# LTC6820.net
KiCad netlist of a schematic drawn in Altium Designer
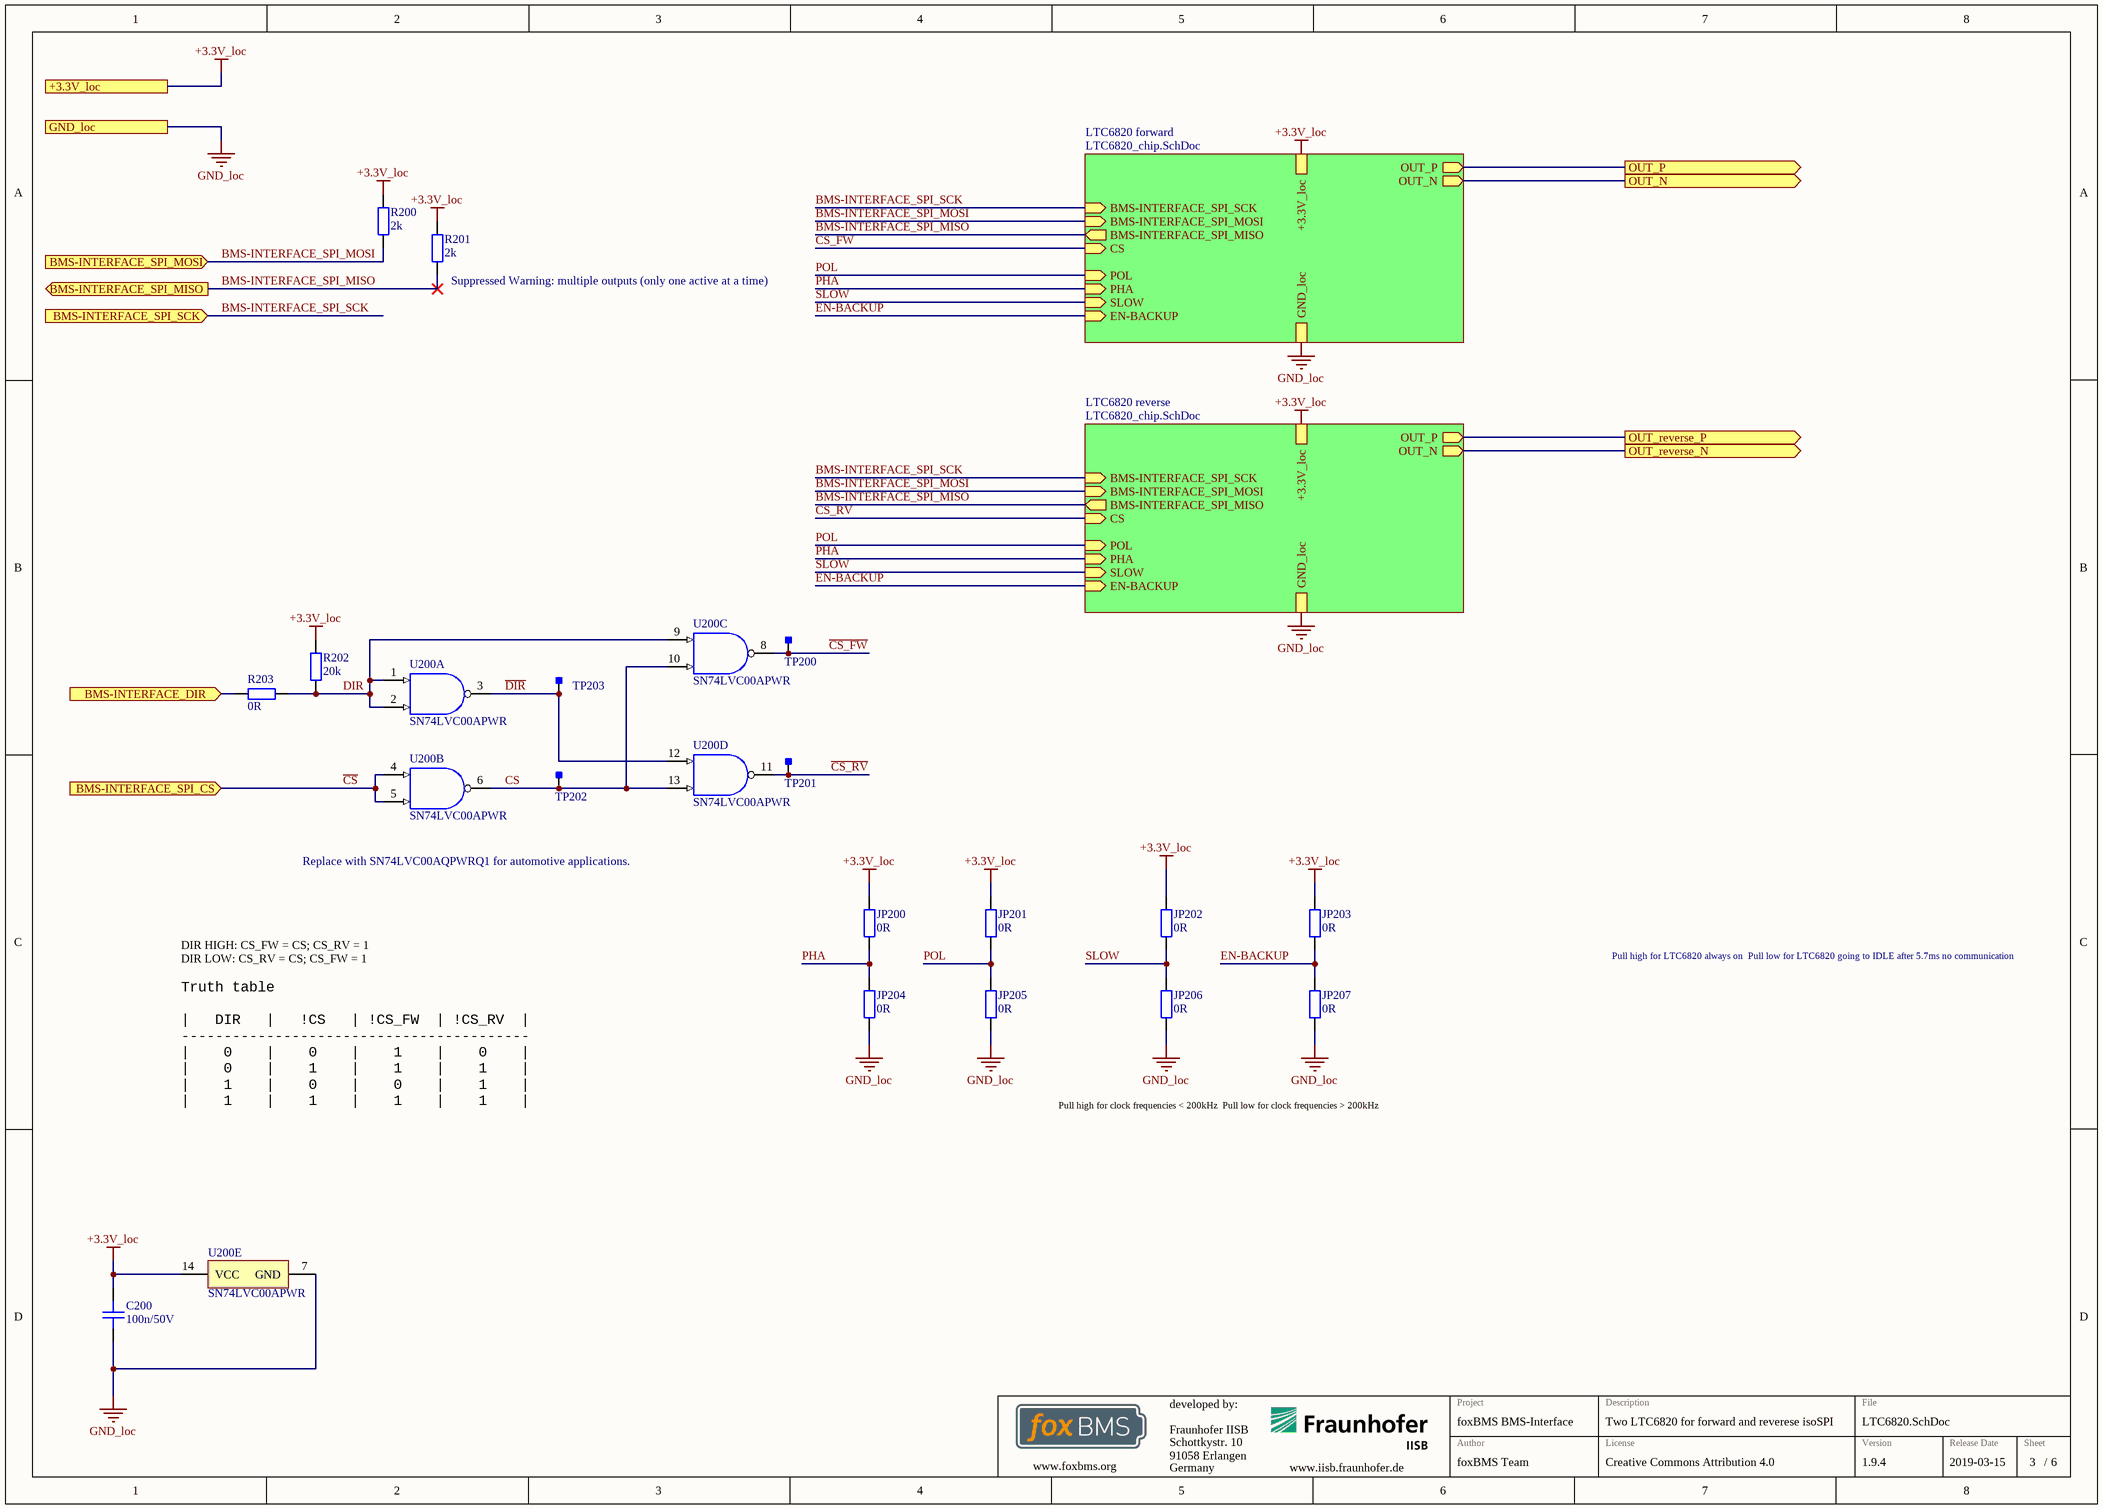
[diagram p0: LTC6820.SchDoc]

(export (version "E")
  (design (tool "Eeschema 10.0.6"))
  (components
    (comp (ref "C200")
      (value "100n/50V")
      (footprint "CAPC1608X08N")
      (description "MLCC")
      (fields (field (name "PART NUMBER") "gen_C_ceramic_100n_50V_X7R_0603"))
      (libsource (lib "OE750") (part "C"))
    )
    (comp (ref "JP200")
      (value "0R")
      (footprint "RESC1608X05N")
      (description "SMD Resistor 0R 0603")
      (fields (field (name "PART NUMBER") "gen_R_0R_0603") (field (name "POWER") "0.1W"))
      (libsource (lib "OE750") (part "R"))
    )
    (comp (ref "JP201")
      (value "0R")
      (footprint "RESC1608X05N")
      (description "SMD Resistor 0R 0603")
      (fields (field (name "PART NUMBER") "gen_R_0R_0603") (field (name "POWER") "0.1W"))
      (libsource (lib "OE750") (part "R"))
    )
    (comp (ref "JP202")
      (value "0R")
      (footprint "RESC1608X05N")
      (description "SMD Resistor 0R 0603")
      (fields (field (name "PART NUMBER") "gen_R_0R_0603") (field (name "POWER") "0.1W"))
      (libsource (lib "OE750") (part "R"))
    )
    (comp (ref "JP203")
      (value "0R")
      (footprint "RESC1608X05N")
      (description "SMD Resistor 0R 0603")
      (fields (field (name "PART NUMBER") "gen_R_0R_0603") (field (name "POWER") "0.1W"))
      (libsource (lib "OE750") (part "R"))
    )
    (comp (ref "JP204")
      (value "0R")
      (footprint "RESC1608X05N")
      (description "SMD Resistor 0R 0603")
      (fields (field (name "PART NUMBER") "gen_R_0R_0603") (field (name "POWER") "0.1W"))
      (libsource (lib "OE750") (part "R"))
    )
    (comp (ref "JP205")
      (value "0R")
      (footprint "RESC1608X05N")
      (description "SMD Resistor 0R 0603")
      (fields (field (name "PART NUMBER") "gen_R_0R_0603") (field (name "POWER") "0.1W"))
      (libsource (lib "OE750") (part "R"))
    )
    (comp (ref "JP206")
      (value "0R")
      (footprint "RESC1608X05N")
      (description "SMD Resistor 0R 0603")
      (fields (field (name "PART NUMBER") "gen_R_0R_0603") (field (name "POWER") "0.1W"))
      (libsource (lib "OE750") (part "R"))
    )
    (comp (ref "JP207")
      (value "0R")
      (footprint "RESC1608X05N")
      (description "SMD Resistor 0R 0603")
      (fields (field (name "PART NUMBER") "gen_R_0R_0603") (field (name "POWER") "0.1W"))
      (libsource (lib "OE750") (part "R"))
    )
    (comp (ref "R200")
      (value "2k")
      (footprint "RESC1608X05N")
      (description "SMD Resistor 2k 0603")
      (fields (field (name "PART NUMBER") "gen_R_2k_0603") (field (name "TOLERANCE") "1%"))
      (libsource (lib "OE750") (part "R"))
    )
    (comp (ref "R201")
      (value "2k")
      (footprint "RESC1608X05N")
      (description "SMD Resistor 2k 0603")
      (fields (field (name "PART NUMBER") "gen_R_2k_0603") (field (name "TOLERANCE") "1%"))
      (libsource (lib "OE750") (part "R"))
    )
    (comp (ref "R202")
      (value "20k")
      (footprint "RESC1608X05N")
      (description "SMD Resistor 20k 0603")
      (fields (field (name "PART NUMBER") "gen_R_20k_0603") (field (name "TOLERANCE") "1%"))
      (libsource (lib "OE750") (part "R"))
    )
    (comp (ref "R203")
      (value "0R")
      (footprint "RESC1608X05N")
      (description "SMD Resistor 0R 0603")
      (fields (field (name "PART NUMBER") "gen_R_0R_0603") (field (name "POWER") "0.1W"))
      (libsource (lib "OE750") (part "R"))
    )
    (comp (ref "TP200")
      (value "Testpoint_Square")
      (footprint "Testpoint_S1")
      (description "Testpoint, square")
      (libsource (lib "OE750") (part "Testpoint_Square"))
    )
    (comp (ref "TP201")
      (value "Testpoint_Square")
      (footprint "Testpoint_S1")
      (description "Testpoint, square")
      (libsource (lib "OE750") (part "Testpoint_Square"))
    )
    (comp (ref "TP202")
      (value "Testpoint_Square")
      (footprint "Testpoint_S1")
      (description "Testpoint, square")
      (libsource (lib "OE750") (part "Testpoint_Square"))
    )
    (comp (ref "TP203")
      (value "Testpoint_Square")
      (footprint "Testpoint_S1")
      (description "Testpoint, square")
      (libsource (lib "OE750") (part "Testpoint_Square"))
    )
    (comp (ref "U200")
      (value "SN74LVC00APWR")
      (footprint "PW0014A_M")
      (description "Quadruple 2-Input Positive-NAND Gate, PW0014A, LARGE T&R")
      (fields
        (field (name "GENERIC PART NUMBER") "SN74LVC00A")
        (field (name "MANUFACTURER") "Texas Instruments")
      )
      (libsource (lib "Altium Content Vault") (part "TI-SN74LVC00A-14"))
    )
  )
  (nets
    (net (code "1") (name "+3.3V_loc") (class "Default")
      (node (ref "C200") (pin "2") (pinfunction "2_2") (pintype "passive"))
      (node (ref "JP200") (pin "2") (pinfunction "2_2") (pintype "passive"))
      (node (ref "JP201") (pin "2") (pinfunction "2_2") (pintype "passive"))
      (node (ref "JP202") (pin "2") (pinfunction "2_2") (pintype "passive"))
      (node (ref "JP203") (pin "2") (pinfunction "2_2") (pintype "passive"))
      (node (ref "R200") (pin "2") (pinfunction "2_2") (pintype "passive"))
      (node (ref "R201") (pin "2") (pinfunction "2_2") (pintype "passive"))
      (node (ref "R202") (pin "2") (pinfunction "2_2") (pintype "passive"))
      (node (ref "U200") (pin "14") (pinfunction "VCC_14") (pintype "power_in"))
    )
    (net (code "2") (name "/BMS-INTERFACE_DIR") (class "Default")
      (node (ref "R203") (pin "1") (pinfunction "1_1") (pintype "passive"))
    )
    (net (code "3") (name "/BMS-INTERFACE_SPI_MISO") (class "Default")
      (node (ref "R201") (pin "1") (pinfunction "1_1") (pintype "passive+no_connect"))
    )
    (net (code "4") (name "/BMS-INTERFACE_SPI_MOSI") (class "Default")
      (node (ref "R200") (pin "1") (pinfunction "1_1") (pintype "passive"))
    )
    (net (code "6") (name "/CS") (class "Default")
      (node (ref "TP202") (pin "1") (pinfunction "1_1") (pintype "passive"))
      (node (ref "U200") (pin "10") (pinfunction "3B_10") (pintype "input"))
      (node (ref "U200") (pin "13") (pinfunction "4B_13") (pintype "input"))
      (node (ref "U200") (pin "6") (pinfunction "2Y_6") (pintype "open_collector"))
    )
    (net (code "7") (name "/DIR") (class "Default")
      (node (ref "R202") (pin "1") (pinfunction "1_1") (pintype "passive"))
      (node (ref "R203") (pin "2") (pinfunction "2_2") (pintype "passive"))
      (node (ref "U200") (pin "1") (pinfunction "1A_1") (pintype "input"))
      (node (ref "U200") (pin "2") (pinfunction "1B_2") (pintype "input"))
      (node (ref "U200") (pin "9") (pinfunction "3A_9") (pintype "input"))
    )
    (net (code "8") (name "/EN-BACKUP") (class "Default")
      (node (ref "JP203") (pin "1") (pinfunction "1_1") (pintype "passive"))
      (node (ref "JP207") (pin "2") (pinfunction "2_2") (pintype "passive"))
    )
    (net (code "13") (name "/PHA") (class "Default")
      (node (ref "JP200") (pin "1") (pinfunction "1_1") (pintype "passive"))
      (node (ref "JP204") (pin "2") (pinfunction "2_2") (pintype "passive"))
    )
    (net (code "14") (name "/POL") (class "Default")
      (node (ref "JP201") (pin "1") (pinfunction "1_1") (pintype "passive"))
      (node (ref "JP205") (pin "2") (pinfunction "2_2") (pintype "passive"))
    )
    (net (code "15") (name "/SLOW") (class "Default")
      (node (ref "JP202") (pin "1") (pinfunction "1_1") (pintype "passive"))
      (node (ref "JP206") (pin "2") (pinfunction "2_2") (pintype "passive"))
    )
    (net (code "16") (name "/~{CS_FW}") (class "Default")
      (node (ref "TP200") (pin "1") (pinfunction "1_1") (pintype "passive"))
      (node (ref "U200") (pin "8") (pinfunction "3Y_8") (pintype "open_collector"))
    )
    (net (code "17") (name "/~{CS_RV}") (class "Default")
      (node (ref "TP201") (pin "1") (pinfunction "1_1") (pintype "passive"))
      (node (ref "U200") (pin "11") (pinfunction "4Y_11") (pintype "open_collector"))
    )
    (net (code "18") (name "/~{CS}") (class "Default")
      (node (ref "U200") (pin "4") (pinfunction "2A_4") (pintype "input"))
      (node (ref "U200") (pin "5") (pinfunction "2B_5") (pintype "input"))
    )
    (net (code "19") (name "/~{DIR}") (class "Default")
      (node (ref "TP203") (pin "1") (pinfunction "1_1") (pintype "passive"))
      (node (ref "U200") (pin "12") (pinfunction "4A_12") (pintype "input"))
      (node (ref "U200") (pin "3") (pinfunction "1Y_3") (pintype "open_collector"))
    )
    (net (code "20") (name "GND_loc") (class "Default")
      (node (ref "C200") (pin "1") (pinfunction "1_1") (pintype "passive"))
      (node (ref "JP204") (pin "1") (pinfunction "1_1") (pintype "passive"))
      (node (ref "JP205") (pin "1") (pinfunction "1_1") (pintype "passive"))
      (node (ref "JP206") (pin "1") (pinfunction "1_1") (pintype "passive"))
      (node (ref "JP207") (pin "1") (pinfunction "1_1") (pintype "passive"))
      (node (ref "U200") (pin "7") (pinfunction "GND_7") (pintype "power_in"))
    )
  )
)
